# climbingRGB.net
KiCad netlist of a schematic drawn in EAGLE
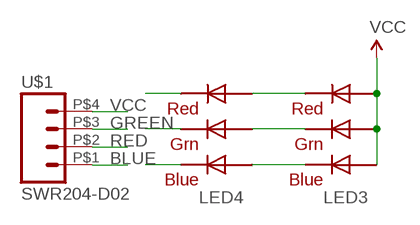
[diagram p0: schematic, sheet 1]

(export (version "E")
  (design (tool "Eeschema 10.0.6"))
  (components
    (comp (ref "LED3")
      (value "RGBLED5050")
      (footprint "eagle-import:RGBLED5050")
      (libsource (lib "eagle-import") (part "RGBLED5050"))
    )
    (comp (ref "LED4")
      (value "RGBLED5050")
      (footprint "eagle-import:RGBLED5050")
      (libsource (lib "eagle-import") (part "RGBLED5050"))
    )
    (comp (ref "U$1")
      (value "SWR204-D02")
      (footprint "eagle-import:SWR204")
      (libsource (lib "eagle-import") (part "SWR204-D02"))
    )
  )
  (nets
    (net (code "1") (name "/BLUE") (class "Default")
      (node (ref "LED4") (pin "4") (pinfunction "BLUE_C_4") (pintype "bidirectional"))
      (node (ref "U$1") (pin "P$1") (pinfunction "1_P$1") (pintype "passive"))
    )
    (net (code "2") (name "/GREEN") (class "Default")
      (node (ref "LED4") (pin "6") (pinfunction "GREEN_C_6") (pintype "bidirectional"))
      (node (ref "U$1") (pin "P$3") (pinfunction "3_P$3") (pintype "passive"))
    )
    (net (code "3") (name "/RED") (class "Default")
      (node (ref "LED4") (pin "5") (pinfunction "RED_C_5") (pintype "bidirectional"))
      (node (ref "U$1") (pin "P$2") (pinfunction "2_P$2") (pintype "passive"))
    )
    (net (code "4") (name "Net-(LED3-BLUE_C)") (class "Default")
      (node (ref "LED3") (pin "4") (pinfunction "BLUE_C_4") (pintype "bidirectional"))
      (node (ref "LED4") (pin "3") (pinfunction "BLUE_A_3") (pintype "bidirectional"))
    )
    (net (code "5") (name "Net-(LED3-GREEN_C)") (class "Default")
      (node (ref "LED3") (pin "6") (pinfunction "GREEN_C_6") (pintype "bidirectional"))
      (node (ref "LED4") (pin "1") (pinfunction "GREEN_A_1") (pintype "bidirectional"))
    )
    (net (code "6") (name "Net-(LED3-RED_C)") (class "Default")
      (node (ref "LED3") (pin "5") (pinfunction "RED_C_5") (pintype "bidirectional"))
      (node (ref "LED4") (pin "2") (pinfunction "RED_A_2") (pintype "bidirectional"))
    )
    (net (code "7") (name "VCC") (class "Default")
      (node (ref "LED3") (pin "1") (pinfunction "GREEN_A_1") (pintype "bidirectional"))
      (node (ref "LED3") (pin "2") (pinfunction "RED_A_2") (pintype "bidirectional"))
      (node (ref "LED3") (pin "3") (pinfunction "BLUE_A_3") (pintype "bidirectional"))
      (node (ref "U$1") (pin "P$4") (pinfunction "4_P$4") (pintype "passive"))
    )
  )
)
